# MultiWiiChassis_messed.net
KiCad netlist of a schematic drawn in EAGLE
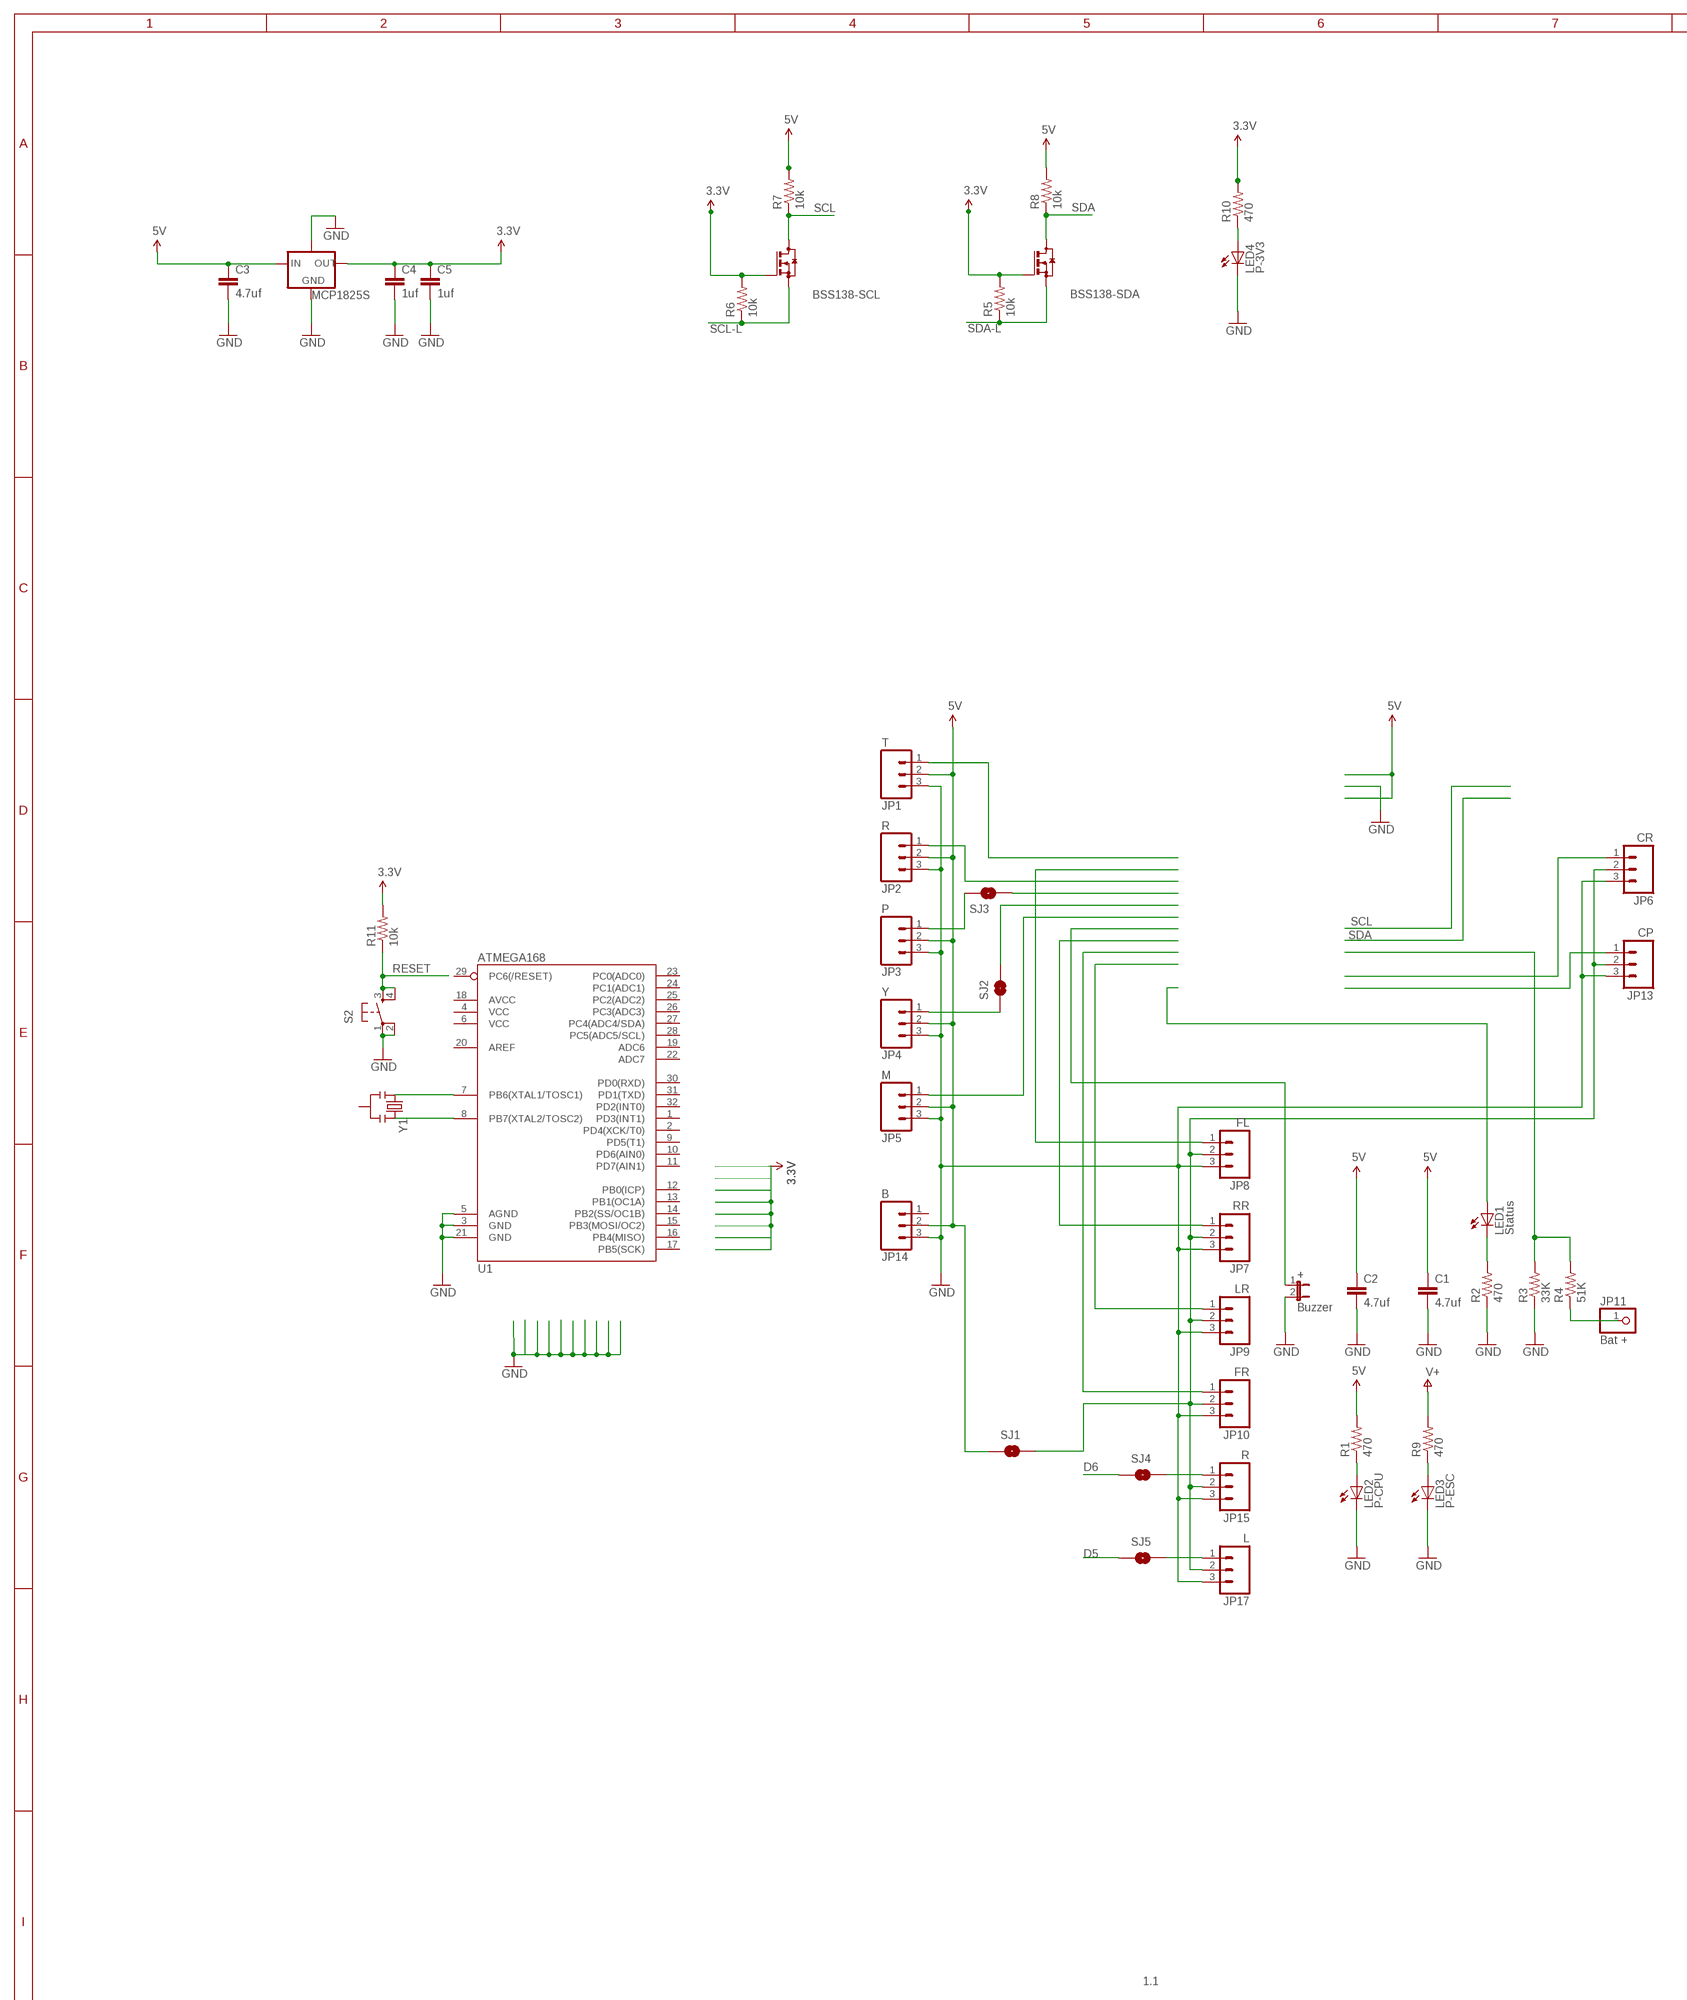
[diagram p0: schematic, sheet 1, part 1 of 2]
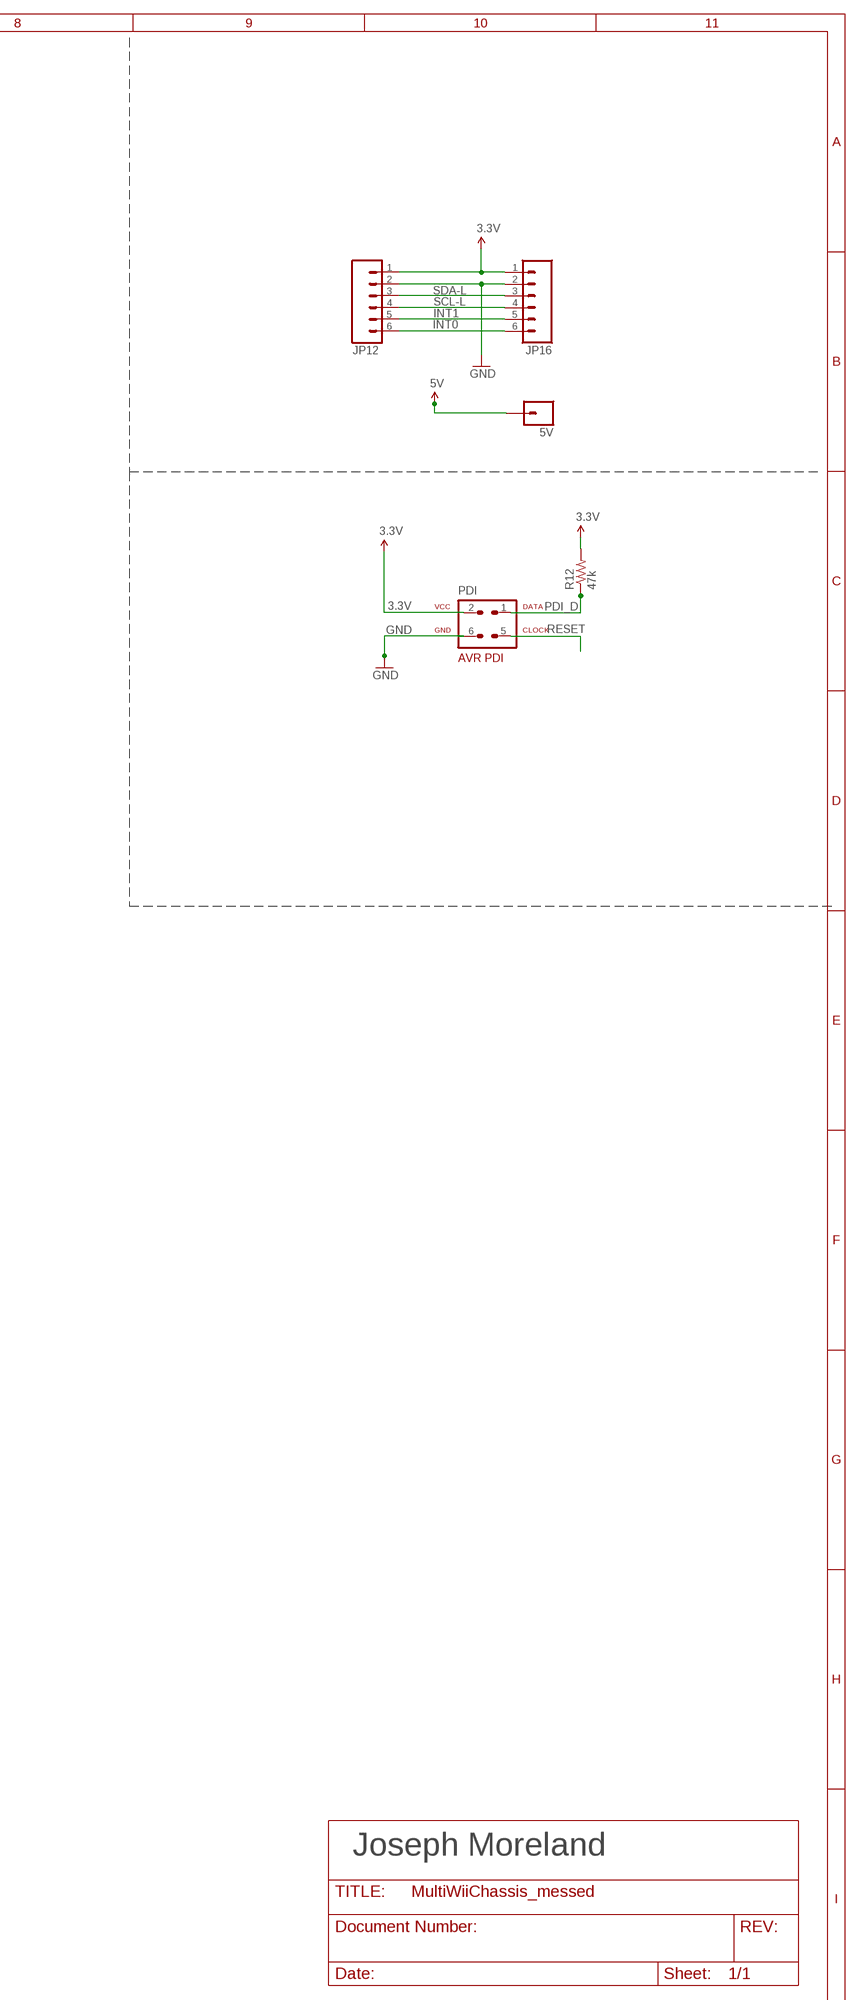
[diagram p1: schematic, sheet 1, part 2 of 2]

(export (version "E")
  (design (tool "Eeschema 10.0.6"))
  (components
    (comp (ref "+")
      (value "Buzzer")
      (footprint "eagle-import:1X02")
      (libsource (lib "eagle-import") (part "JUMPER-2PTH"))
    )
    (comp (ref "5V")
      (value "M01PTH")
      (footprint "eagle-import:1X01")
      (libsource (lib "eagle-import") (part "M01PTH"))
    )
    (comp (ref "BSS138-SCL")
      (value "BSS138BOTTOM")
      (footprint "eagle-import:SOT23_BOT")
      (libsource (lib "eagle-import") (part "BSS138BOTTOM"))
    )
    (comp (ref "BSS138-SDA")
      (value "BSS138BOTTOM")
      (footprint "eagle-import:SOT23_BOT")
      (libsource (lib "eagle-import") (part "BSS138BOTTOM"))
    )
    (comp (ref "C1")
      (value "4.7uf")
      (footprint "eagle-import:0805")
      (libsource (lib "eagle-import") (part "CAP0805"))
    )
    (comp (ref "C2")
      (value "4.7uf")
      (footprint "eagle-import:0805")
      (libsource (lib "eagle-import") (part "CAP0805"))
    )
    (comp (ref "C3")
      (value "4.7uf")
      (footprint "eagle-import:0805")
      (libsource (lib "eagle-import") (part "CAP0805"))
    )
    (comp (ref "C4")
      (value "1uf")
      (footprint "eagle-import:0805")
      (libsource (lib "eagle-import") (part "CAP0805"))
    )
    (comp (ref "C5")
      (value "1uf")
      (footprint "eagle-import:0805")
      (libsource (lib "eagle-import") (part "CAP0805"))
    )
    (comp (ref "JP1")
      (value "T")
      (footprint "eagle-import:1X03")
      (libsource (lib "eagle-import") (part "M03PTH"))
    )
    (comp (ref "JP2")
      (value "R")
      (footprint "eagle-import:1X03")
      (libsource (lib "eagle-import") (part "M03PTH"))
    )
    (comp (ref "JP3")
      (value "P")
      (footprint "eagle-import:1X03")
      (libsource (lib "eagle-import") (part "M03PTH"))
    )
    (comp (ref "JP4")
      (value "Y")
      (footprint "eagle-import:1X03")
      (libsource (lib "eagle-import") (part "M03PTH"))
    )
    (comp (ref "JP5")
      (value "M")
      (footprint "eagle-import:1X03")
      (libsource (lib "eagle-import") (part "M03PTH"))
    )
    (comp (ref "JP6")
      (value "CR")
      (footprint "eagle-import:1X03")
      (libsource (lib "eagle-import") (part "M03PTH"))
    )
    (comp (ref "JP7")
      (value "RR")
      (footprint "eagle-import:1X03")
      (libsource (lib "eagle-import") (part "M03PTH"))
    )
    (comp (ref "JP8")
      (value "FL")
      (footprint "eagle-import:1X03")
      (libsource (lib "eagle-import") (part "M03PTH"))
    )
    (comp (ref "JP9")
      (value "LR")
      (footprint "eagle-import:1X03")
      (libsource (lib "eagle-import") (part "M03PTH"))
    )
    (comp (ref "JP10")
      (value "FR")
      (footprint "eagle-import:1X03")
      (libsource (lib "eagle-import") (part "M03PTH"))
    )
    (comp (ref "JP11")
      (value "Bat +")
      (footprint "eagle-import:1X01")
      (libsource (lib "eagle-import") (part "PINHD-1X1"))
    )
    (comp (ref "JP12")
      (value "M06LOCK")
      (footprint "eagle-import:1X06_LOCK")
      (libsource (lib "eagle-import") (part "M06LOCK"))
    )
    (comp (ref "JP13")
      (value "CP")
      (footprint "eagle-import:1X03")
      (libsource (lib "eagle-import") (part "M03PTH"))
    )
    (comp (ref "JP14")
      (value "B")
      (footprint "eagle-import:1X03")
      (libsource (lib "eagle-import") (part "M03PTH"))
    )
    (comp (ref "JP15")
      (value "R")
      (footprint "eagle-import:1X03")
      (libsource (lib "eagle-import") (part "M03PTH"))
    )
    (comp (ref "JP16")
      (value "M06LOCK")
      (footprint "eagle-import:1X06_LOCK")
      (libsource (lib "eagle-import") (part "M06LOCK"))
    )
    (comp (ref "JP17")
      (value "L")
      (footprint "eagle-import:1X03")
      (libsource (lib "eagle-import") (part "M03PTH"))
    )
    (comp (ref "LED1")
      (value "Status")
      (footprint "eagle-import:LED-1206")
      (libsource (lib "eagle-import") (part "LED1206"))
    )
    (comp (ref "LED2")
      (value "P-CPU")
      (footprint "eagle-import:LED-1206")
      (libsource (lib "eagle-import") (part "LED1206"))
    )
    (comp (ref "LED3")
      (value "P-ESC")
      (footprint "eagle-import:LED-1206")
      (libsource (lib "eagle-import") (part "LED1206"))
    )
    (comp (ref "LED4")
      (value "P-3V3")
      (footprint "eagle-import:LED-1206")
      (libsource (lib "eagle-import") (part "LED1206"))
    )
    (comp (ref "MCP1825S")
      (value "V_REG_MCP1825S")
      (footprint "eagle-import:SOT223_BOT")
      (libsource (lib "eagle-import") (part "V_REG_MCP1825SBOTTOM"))
    )
    (comp (ref "PDI")
      (value "AVR-PDIVERT")
      (footprint "eagle-import:AVR-ISP-6")
      (libsource (lib "eagle-import") (part "AVR-PDIVERT"))
    )
    (comp (ref "R1")
      (value "470")
      (footprint "eagle-import:0805")
      (libsource (lib "eagle-import") (part "RESISTOR0805-RES"))
    )
    (comp (ref "R2")
      (value "470")
      (footprint "eagle-import:0805")
      (libsource (lib "eagle-import") (part "RESISTOR0805-RES"))
    )
    (comp (ref "R3")
      (value "33K")
      (footprint "eagle-import:0805")
      (libsource (lib "eagle-import") (part "RESISTOR0805-RES"))
    )
    (comp (ref "R4")
      (value "51K")
      (footprint "eagle-import:0805")
      (libsource (lib "eagle-import") (part "RESISTOR0805-RES"))
    )
    (comp (ref "R5")
      (value "10k")
      (footprint "eagle-import:0805")
      (libsource (lib "eagle-import") (part "RESISTOR0805-RES"))
    )
    (comp (ref "R6")
      (value "10k")
      (footprint "eagle-import:0805")
      (libsource (lib "eagle-import") (part "RESISTOR0805-RES"))
    )
    (comp (ref "R7")
      (value "10k")
      (footprint "eagle-import:0805")
      (libsource (lib "eagle-import") (part "RESISTOR0805-RES"))
    )
    (comp (ref "R8")
      (value "10k")
      (footprint "eagle-import:0805")
      (libsource (lib "eagle-import") (part "RESISTOR0805-RES"))
    )
    (comp (ref "R9")
      (value "470")
      (footprint "eagle-import:0805")
      (libsource (lib "eagle-import") (part "RESISTOR0805-RES"))
    )
    (comp (ref "R10")
      (value "470")
      (footprint "eagle-import:0805")
      (libsource (lib "eagle-import") (part "RESISTOR0805-RES"))
    )
    (comp (ref "R11")
      (value "10k")
      (footprint "eagle-import:0603-RES")
      (libsource (lib "eagle-import") (part "RESISTOR0603-RES"))
    )
    (comp (ref "R12")
      (value "47k")
      (footprint "eagle-import:0603-RES")
      (libsource (lib "eagle-import") (part "RESISTOR0603-RES"))
    )
    (comp (ref "S2")
      (value "TAC_SWITCHSMD")
      (footprint "eagle-import:TACTILE_SWITCH_SMD")
      (libsource (lib "eagle-import") (part "TAC_SWITCHSMD"))
    )
    (comp (ref "SJ1")
      (value "SOLDERJUMPERNO")
      (footprint "eagle-import:SJ_2S-NO")
      (libsource (lib "eagle-import") (part "SOLDERJUMPERNO"))
    )
    (comp (ref "SJ2")
      (value "SOLDERJUMPERNO")
      (footprint "eagle-import:SJ_2S-NO")
      (libsource (lib "eagle-import") (part "SOLDERJUMPERNO"))
    )
    (comp (ref "SJ3")
      (value "SOLDERJUMPERNO")
      (footprint "eagle-import:SJ_2S-NO")
      (libsource (lib "eagle-import") (part "SOLDERJUMPERNO"))
    )
    (comp (ref "SJ4")
      (value "SOLDERJUMPERNO")
      (footprint "eagle-import:SJ_2S-NO")
      (libsource (lib "eagle-import") (part "SOLDERJUMPERNO"))
    )
    (comp (ref "SJ5")
      (value "SOLDERJUMPERNO")
      (footprint "eagle-import:SJ_2S-NO")
      (libsource (lib "eagle-import") (part "SOLDERJUMPERNO"))
    )
    (comp (ref "U1")
      (value "ATMEGA168")
      (footprint "eagle-import:TQFP32-08")
      (libsource (lib "eagle-import") (part "ATMEGA168"))
    )
    (comp (ref "Y1")
      (value "RESONATORSMD")
      (footprint "eagle-import:RESONATOR-SMD")
      (libsource (lib "eagle-import") (part "RESONATORSMD"))
    )
  )
  (nets
    (net (code "1") (name "/D5") (class "Default")
      (node (ref "SJ3") (pin "2") (pinfunction "2_2") (pintype "passive"))
      (node (ref "SJ5") (pin "1") (pinfunction "1_1") (pintype "passive"))
    )
    (net (code "2") (name "/D6") (class "Default")
      (node (ref "SJ2") (pin "2") (pinfunction "2_2") (pintype "passive"))
      (node (ref "SJ4") (pin "1") (pinfunction "1_1") (pintype "passive"))
    )
    (net (code "3") (name "/INT0") (class "Default")
      (node (ref "JP12") (pin "6") (pinfunction "6_6") (pintype "passive"))
      (node (ref "JP16") (pin "6") (pinfunction "6_6") (pintype "passive"))
    )
    (net (code "4") (name "/INT1") (class "Default")
      (node (ref "JP12") (pin "5") (pinfunction "5_5") (pintype "passive"))
      (node (ref "JP16") (pin "5") (pinfunction "5_5") (pintype "passive"))
    )
    (net (code "5") (name "/PDI_D") (class "Default")
      (node (ref "PDI") (pin "1") (pinfunction "1_1") (pintype "passive"))
      (node (ref "R12") (pin "1") (pinfunction "1_1") (pintype "passive"))
    )
    (net (code "6") (name "/RESET") (class "Default")
      (node (ref "PDI") (pin "5") (pinfunction "5_5") (pintype "passive"))
      (node (ref "R11") (pin "1") (pinfunction "1_1") (pintype "passive"))
      (node (ref "S2") (pin "3") (pinfunction "3_3") (pintype "passive"))
      (node (ref "S2") (pin "4") (pinfunction "4_4") (pintype "passive"))
    )
    (net (code "7") (name "/SCL") (class "Default")
      (node (ref "BSS138-SCL") (pin "D") (pinfunction "D_D") (pintype "passive"))
      (node (ref "R7") (pin "1") (pinfunction "1_1") (pintype "passive"))
    )
    (net (code "8") (name "/SCL-L") (class "Default")
      (node (ref "BSS138-SCL") (pin "S") (pinfunction "S_S") (pintype "passive"))
      (node (ref "JP12") (pin "4") (pinfunction "4_4") (pintype "passive"))
      (node (ref "JP16") (pin "4") (pinfunction "4_4") (pintype "passive"))
      (node (ref "R6") (pin "1") (pinfunction "1_1") (pintype "passive"))
    )
    (net (code "9") (name "/SDA") (class "Default")
      (node (ref "BSS138-SDA") (pin "D") (pinfunction "D_D") (pintype "passive"))
      (node (ref "R8") (pin "1") (pinfunction "1_1") (pintype "passive"))
    )
    (net (code "10") (name "/SDA-L") (class "Default")
      (node (ref "BSS138-SDA") (pin "S") (pinfunction "S_S") (pintype "passive"))
      (node (ref "JP12") (pin "3") (pinfunction "3_3") (pintype "passive"))
      (node (ref "JP16") (pin "3") (pinfunction "3_3") (pintype "passive"))
      (node (ref "R5") (pin "1") (pinfunction "1_1") (pintype "passive"))
    )
    (net (code "11") (name "3.3V") (class "Default")
      (node (ref "BSS138-SCL") (pin "G") (pinfunction "G_G") (pintype "passive"))
      (node (ref "BSS138-SDA") (pin "G") (pinfunction "G_G") (pintype "passive"))
      (node (ref "C4") (pin "1") (pinfunction "1_1") (pintype "passive"))
      (node (ref "C5") (pin "1") (pinfunction "1_1") (pintype "passive"))
      (node (ref "JP12") (pin "1") (pinfunction "1_1") (pintype "passive"))
      (node (ref "JP16") (pin "1") (pinfunction "1_1") (pintype "passive"))
      (node (ref "MCP1825S") (pin "3") (pinfunction "OUT_3") (pintype "power_in"))
      (node (ref "PDI") (pin "2") (pinfunction "2_2") (pintype "passive"))
      (node (ref "R10") (pin "2") (pinfunction "2_2") (pintype "passive"))
      (node (ref "R11") (pin "2") (pinfunction "2_2") (pintype "passive"))
      (node (ref "R12") (pin "2") (pinfunction "2_2") (pintype "passive"))
      (node (ref "R5") (pin "2") (pinfunction "2_2") (pintype "passive"))
      (node (ref "R6") (pin "2") (pinfunction "2_2") (pintype "passive"))
    )
    (net (code "12") (name "5V") (class "Default")
      (node (ref "5V") (pin "1") (pinfunction "1_1") (pintype "passive"))
      (node (ref "C1") (pin "1") (pinfunction "1_1") (pintype "passive"))
      (node (ref "C2") (pin "1") (pinfunction "1_1") (pintype "passive"))
      (node (ref "C3") (pin "1") (pinfunction "1_1") (pintype "passive"))
      (node (ref "JP1") (pin "2") (pinfunction "2_2") (pintype "passive"))
      (node (ref "JP14") (pin "2") (pinfunction "2_2") (pintype "passive"))
      (node (ref "JP2") (pin "2") (pinfunction "2_2") (pintype "passive"))
      (node (ref "JP3") (pin "2") (pinfunction "2_2") (pintype "passive"))
      (node (ref "JP4") (pin "2") (pinfunction "2_2") (pintype "passive"))
      (node (ref "JP5") (pin "2") (pinfunction "2_2") (pintype "passive"))
      (node (ref "MCP1825S") (pin "1") (pinfunction "IN_1") (pintype "input"))
      (node (ref "R1") (pin "2") (pinfunction "2_2") (pintype "passive"))
      (node (ref "R7") (pin "2") (pinfunction "2_2") (pintype "passive"))
      (node (ref "R8") (pin "2") (pinfunction "2_2") (pintype "passive"))
      (node (ref "SJ1") (pin "1") (pinfunction "1_1") (pintype "passive"))
    )
    (net (code "13") (name "GND") (class "Default")
      (node (ref "+") (pin "2") (pinfunction "2_2") (pintype "passive"))
      (node (ref "C1") (pin "2") (pinfunction "2_2") (pintype "passive"))
      (node (ref "C2") (pin "2") (pinfunction "2_2") (pintype "passive"))
      (node (ref "C3") (pin "2") (pinfunction "2_2") (pintype "passive"))
      (node (ref "C4") (pin "2") (pinfunction "2_2") (pintype "passive"))
      (node (ref "C5") (pin "2") (pinfunction "2_2") (pintype "passive"))
      (node (ref "JP1") (pin "3") (pinfunction "3_3") (pintype "passive"))
      (node (ref "JP10") (pin "3") (pinfunction "3_3") (pintype "passive"))
      (node (ref "JP12") (pin "2") (pinfunction "2_2") (pintype "passive"))
      (node (ref "JP13") (pin "3") (pinfunction "3_3") (pintype "passive"))
      (node (ref "JP14") (pin "3") (pinfunction "3_3") (pintype "passive"))
      (node (ref "JP15") (pin "3") (pinfunction "3_3") (pintype "passive"))
      (node (ref "JP16") (pin "2") (pinfunction "2_2") (pintype "passive"))
      (node (ref "JP17") (pin "3") (pinfunction "3_3") (pintype "passive"))
      (node (ref "JP2") (pin "3") (pinfunction "3_3") (pintype "passive"))
      (node (ref "JP3") (pin "3") (pinfunction "3_3") (pintype "passive"))
      (node (ref "JP4") (pin "3") (pinfunction "3_3") (pintype "passive"))
      (node (ref "JP5") (pin "3") (pinfunction "3_3") (pintype "passive"))
      (node (ref "JP6") (pin "3") (pinfunction "3_3") (pintype "passive"))
      (node (ref "JP7") (pin "3") (pinfunction "3_3") (pintype "passive"))
      (node (ref "JP8") (pin "3") (pinfunction "3_3") (pintype "passive"))
      (node (ref "JP9") (pin "3") (pinfunction "3_3") (pintype "passive"))
      (node (ref "LED2") (pin "C") (pinfunction "C_C") (pintype "passive"))
      (node (ref "LED3") (pin "C") (pinfunction "C_C") (pintype "passive"))
      (node (ref "LED4") (pin "C") (pinfunction "C_C") (pintype "passive"))
      (node (ref "MCP1825S") (pin "2") (pinfunction "GND_2") (pintype "input"))
      (node (ref "MCP1825S") (pin "GNDPAD") (pinfunction "GNDPAD_GNDPAD") (pintype "bidirectional"))
      (node (ref "PDI") (pin "6") (pinfunction "6_6") (pintype "passive"))
      (node (ref "R2") (pin "1") (pinfunction "1_1") (pintype "passive"))
      (node (ref "R3") (pin "1") (pinfunction "1_1") (pintype "passive"))
      (node (ref "S2") (pin "1") (pinfunction "1_1") (pintype "passive"))
      (node (ref "S2") (pin "2") (pinfunction "2_2") (pintype "passive"))
      (node (ref "U1") (pin "21") (pinfunction "GND_21") (pintype "bidirectional"))
      (node (ref "U1") (pin "3") (pinfunction "GND_3") (pintype "bidirectional"))
      (node (ref "U1") (pin "5") (pinfunction "AGND_5") (pintype "bidirectional"))
    )
    (net (code "14") (name "Net-(JP3-Pad1)") (class "Default")
      (node (ref "JP3") (pin "1") (pinfunction "1_1") (pintype "passive"))
      (node (ref "SJ3") (pin "1") (pinfunction "1_1") (pintype "passive"))
    )
    (net (code "15") (name "Net-(JP4-Pad1)") (class "Default")
      (node (ref "JP4") (pin "1") (pinfunction "1_1") (pintype "passive"))
      (node (ref "SJ2") (pin "1") (pinfunction "1_1") (pintype "passive"))
    )
    (net (code "16") (name "Net-(JP11-Pad1)") (class "Default")
      (node (ref "JP11") (pin "1") (pinfunction "1_1") (pintype "passive"))
      (node (ref "R4") (pin "1") (pinfunction "1_1") (pintype "passive"))
    )
    (net (code "17") (name "Net-(JP15-Pad1)") (class "Default")
      (node (ref "JP15") (pin "1") (pinfunction "1_1") (pintype "passive"))
      (node (ref "SJ4") (pin "2") (pinfunction "2_2") (pintype "passive"))
    )
    (net (code "18") (name "Net-(JP17-Pad1)") (class "Default")
      (node (ref "JP17") (pin "1") (pinfunction "1_1") (pintype "passive"))
      (node (ref "SJ5") (pin "2") (pinfunction "2_2") (pintype "passive"))
    )
    (net (code "19") (name "Net-(LED1-PadC)") (class "Default")
      (node (ref "LED1") (pin "C") (pinfunction "C_C") (pintype "passive"))
      (node (ref "R2") (pin "2") (pinfunction "2_2") (pintype "passive"))
    )
    (net (code "20") (name "Net-(LED2-PadA)") (class "Default")
      (node (ref "LED2") (pin "A") (pinfunction "A_A") (pintype "passive"))
      (node (ref "R1") (pin "1") (pinfunction "1_1") (pintype "passive"))
    )
    (net (code "21") (name "Net-(LED3-PadA)") (class "Default")
      (node (ref "LED3") (pin "A") (pinfunction "A_A") (pintype "passive"))
      (node (ref "R9") (pin "1") (pinfunction "1_1") (pintype "passive"))
    )
    (net (code "22") (name "Net-(LED4-PadA)") (class "Default")
      (node (ref "LED4") (pin "A") (pinfunction "A_A") (pintype "passive"))
      (node (ref "R10") (pin "1") (pinfunction "1_1") (pintype "passive"))
    )
    (net (code "23") (name "Net-(R3-Pad2)") (class "Default")
      (node (ref "R3") (pin "2") (pinfunction "2_2") (pintype "passive"))
      (node (ref "R4") (pin "2") (pinfunction "2_2") (pintype "passive"))
    )
    (net (code "24") (name "Net-(U1-PB6(XTAL1{slash}TOSC1))") (class "Default")
      (node (ref "U1") (pin "7") (pinfunction "PB6(XTAL1/TOSC1)_7") (pintype "bidirectional"))
      (node (ref "Y1") (pin "1") (pinfunction "1_1") (pintype "passive"))
    )
    (net (code "25") (name "Net-(U1-PB7(XTAL2{slash}TOSC2))") (class "Default")
      (node (ref "U1") (pin "8") (pinfunction "PB7(XTAL2/TOSC2)_8") (pintype "bidirectional"))
      (node (ref "Y1") (pin "3") (pinfunction "3_3") (pintype "passive"))
    )
    (net (code "26") (name "V+") (class "Default")
      (node (ref "JP10") (pin "2") (pinfunction "2_2") (pintype "passive"))
      (node (ref "JP13") (pin "2") (pinfunction "2_2") (pintype "passive"))
      (node (ref "JP15") (pin "2") (pinfunction "2_2") (pintype "passive"))
      (node (ref "JP17") (pin "2") (pinfunction "2_2") (pintype "passive"))
      (node (ref "JP6") (pin "2") (pinfunction "2_2") (pintype "passive"))
      (node (ref "JP7") (pin "2") (pinfunction "2_2") (pintype "passive"))
      (node (ref "JP8") (pin "2") (pinfunction "2_2") (pintype "passive"))
      (node (ref "JP9") (pin "2") (pinfunction "2_2") (pintype "passive"))
      (node (ref "R9") (pin "2") (pinfunction "2_2") (pintype "passive"))
      (node (ref "SJ1") (pin "2") (pinfunction "2_2") (pintype "passive"))
    )
    (net (code "27") (name "unconnected-(+-Pad1)") (class "Default")
      (node (ref "+") (pin "1") (pinfunction "1_1") (pintype "passive"))
    )
    (net (code "28") (name "unconnected-(JP1-Pad1)") (class "Default")
      (node (ref "JP1") (pin "1") (pinfunction "1_1") (pintype "passive"))
    )
    (net (code "29") (name "unconnected-(JP2-Pad1)") (class "Default")
      (node (ref "JP2") (pin "1") (pinfunction "1_1") (pintype "passive"))
    )
    (net (code "30") (name "unconnected-(JP5-Pad1)") (class "Default")
      (node (ref "JP5") (pin "1") (pinfunction "1_1") (pintype "passive"))
    )
    (net (code "31") (name "unconnected-(JP6-Pad1)") (class "Default")
      (node (ref "JP6") (pin "1") (pinfunction "1_1") (pintype "passive"))
    )
    (net (code "32") (name "unconnected-(JP7-Pad1)") (class "Default")
      (node (ref "JP7") (pin "1") (pinfunction "1_1") (pintype "passive"))
    )
    (net (code "33") (name "unconnected-(JP8-Pad1)") (class "Default")
      (node (ref "JP8") (pin "1") (pinfunction "1_1") (pintype "passive"))
    )
    (net (code "34") (name "unconnected-(JP9-Pad1)") (class "Default")
      (node (ref "JP9") (pin "1") (pinfunction "1_1") (pintype "passive"))
    )
    (net (code "35") (name "unconnected-(JP10-Pad1)") (class "Default")
      (node (ref "JP10") (pin "1") (pinfunction "1_1") (pintype "passive"))
    )
    (net (code "36") (name "unconnected-(JP13-Pad1)") (class "Default")
      (node (ref "JP13") (pin "1") (pinfunction "1_1") (pintype "passive"))
    )
    (net (code "37") (name "unconnected-(JP14-Pad1)") (class "Default")
      (node (ref "JP14") (pin "1") (pinfunction "1_1") (pintype "passive"))
    )
    (net (code "38") (name "unconnected-(LED1-PadA)") (class "Default")
      (node (ref "LED1") (pin "A") (pinfunction "A_A") (pintype "passive"))
    )
    (net (code "39") (name "unconnected-(U1-ADC6-Pad19)") (class "Default")
      (node (ref "U1") (pin "19") (pinfunction "ADC6_19") (pintype "bidirectional"))
    )
    (net (code "40") (name "unconnected-(U1-ADC7-Pad22)") (class "Default")
      (node (ref "U1") (pin "22") (pinfunction "ADC7_22") (pintype "bidirectional"))
    )
    (net (code "41") (name "unconnected-(U1-AREF-Pad20)") (class "Default")
      (node (ref "U1") (pin "20") (pinfunction "AREF_20") (pintype "bidirectional"))
    )
    (net (code "42") (name "unconnected-(U1-AVCC-Pad18)") (class "Default")
      (node (ref "U1") (pin "18") (pinfunction "AVCC_18") (pintype "bidirectional"))
    )
    (net (code "43") (name "unconnected-(U1-PB0(ICP)-Pad12)") (class "Default")
      (node (ref "U1") (pin "12") (pinfunction "PB0(ICP)_12") (pintype "bidirectional"))
    )
    (net (code "44") (name "unconnected-(U1-PB1(OC1A)-Pad13)") (class "Default")
      (node (ref "U1") (pin "13") (pinfunction "PB1(OC1A)_13") (pintype "bidirectional"))
    )
    (net (code "45") (name "unconnected-(U1-PB2(SS{slash}OC1B)-Pad14)") (class "Default")
      (node (ref "U1") (pin "14") (pinfunction "PB2(SS/OC1B)_14") (pintype "bidirectional"))
    )
    (net (code "46") (name "unconnected-(U1-PB3(MOSI{slash}OC2)-Pad15)") (class "Default")
      (node (ref "U1") (pin "15") (pinfunction "PB3(MOSI/OC2)_15") (pintype "bidirectional"))
    )
    (net (code "47") (name "unconnected-(U1-PB4(MISO)-Pad16)") (class "Default")
      (node (ref "U1") (pin "16") (pinfunction "PB4(MISO)_16") (pintype "bidirectional"))
    )
    (net (code "48") (name "unconnected-(U1-PB5(SCK)-Pad17)") (class "Default")
      (node (ref "U1") (pin "17") (pinfunction "PB5(SCK)_17") (pintype "bidirectional"))
    )
    (net (code "49") (name "unconnected-(U1-PC0(ADC0)-Pad23)") (class "Default")
      (node (ref "U1") (pin "23") (pinfunction "PC0(ADC0)_23") (pintype "bidirectional"))
    )
    (net (code "50") (name "unconnected-(U1-PC1(ADC1)-Pad24)") (class "Default")
      (node (ref "U1") (pin "24") (pinfunction "PC1(ADC1)_24") (pintype "bidirectional"))
    )
    (net (code "51") (name "unconnected-(U1-PC2(ADC2)-Pad25)") (class "Default")
      (node (ref "U1") (pin "25") (pinfunction "PC2(ADC2)_25") (pintype "bidirectional"))
    )
    (net (code "52") (name "unconnected-(U1-PC3(ADC3)-Pad26)") (class "Default")
      (node (ref "U1") (pin "26") (pinfunction "PC3(ADC3)_26") (pintype "bidirectional"))
    )
    (net (code "53") (name "unconnected-(U1-PC4(ADC4{slash}SDA)-Pad27)") (class "Default")
      (node (ref "U1") (pin "27") (pinfunction "PC4(ADC4/SDA)_27") (pintype "bidirectional"))
    )
    (net (code "54") (name "unconnected-(U1-PC5(ADC5{slash}SCL)-Pad28)") (class "Default")
      (node (ref "U1") (pin "28") (pinfunction "PC5(ADC5/SCL)_28") (pintype "bidirectional"))
    )
    (net (code "55") (name "unconnected-(U1-PC6({slash}RESET)-Pad29)") (class "Default")
      (node (ref "U1") (pin "29") (pinfunction "PC6(/RESET)_29") (pintype "bidirectional"))
    )
    (net (code "56") (name "unconnected-(U1-PD0(RXD)-Pad30)") (class "Default")
      (node (ref "U1") (pin "30") (pinfunction "PD0(RXD)_30") (pintype "bidirectional"))
    )
    (net (code "57") (name "unconnected-(U1-PD1(TXD)-Pad31)") (class "Default")
      (node (ref "U1") (pin "31") (pinfunction "PD1(TXD)_31") (pintype "bidirectional"))
    )
    (net (code "58") (name "unconnected-(U1-PD2(INT0)-Pad32)") (class "Default")
      (node (ref "U1") (pin "32") (pinfunction "PD2(INT0)_32") (pintype "bidirectional"))
    )
    (net (code "59") (name "unconnected-(U1-PD3(INT1)-Pad1)") (class "Default")
      (node (ref "U1") (pin "1") (pinfunction "PD3(INT1)_1") (pintype "bidirectional"))
    )
    (net (code "60") (name "unconnected-(U1-PD4(XCK{slash}T0)-Pad2)") (class "Default")
      (node (ref "U1") (pin "2") (pinfunction "PD4(XCK/T0)_2") (pintype "bidirectional"))
    )
    (net (code "61") (name "unconnected-(U1-PD5(T1)-Pad9)") (class "Default")
      (node (ref "U1") (pin "9") (pinfunction "PD5(T1)_9") (pintype "bidirectional"))
    )
    (net (code "62") (name "unconnected-(U1-PD6(AIN0)-Pad10)") (class "Default")
      (node (ref "U1") (pin "10") (pinfunction "PD6(AIN0)_10") (pintype "bidirectional"))
    )
    (net (code "63") (name "unconnected-(U1-PD7(AIN1)-Pad11)") (class "Default")
      (node (ref "U1") (pin "11") (pinfunction "PD7(AIN1)_11") (pintype "bidirectional"))
    )
    (net (code "64") (name "unconnected-(U1-VCC-Pad4)") (class "Default")
      (node (ref "U1") (pin "4") (pinfunction "VCC_4") (pintype "bidirectional"))
    )
    (net (code "65") (name "unconnected-(U1-VCC-Pad6)") (class "Default")
      (node (ref "U1") (pin "6") (pinfunction "VCC_6") (pintype "bidirectional"))
    )
    (net (code "66") (name "unconnected-(Y1-Pad2)") (class "Default")
      (node (ref "Y1") (pin "2") (pinfunction "2_2") (pintype "passive"))
    )
  )
)
